# snc98_Display_15x7-Seg_3-digit_LTD056.net
KiCad netlist of a schematic drawn in EAGLE
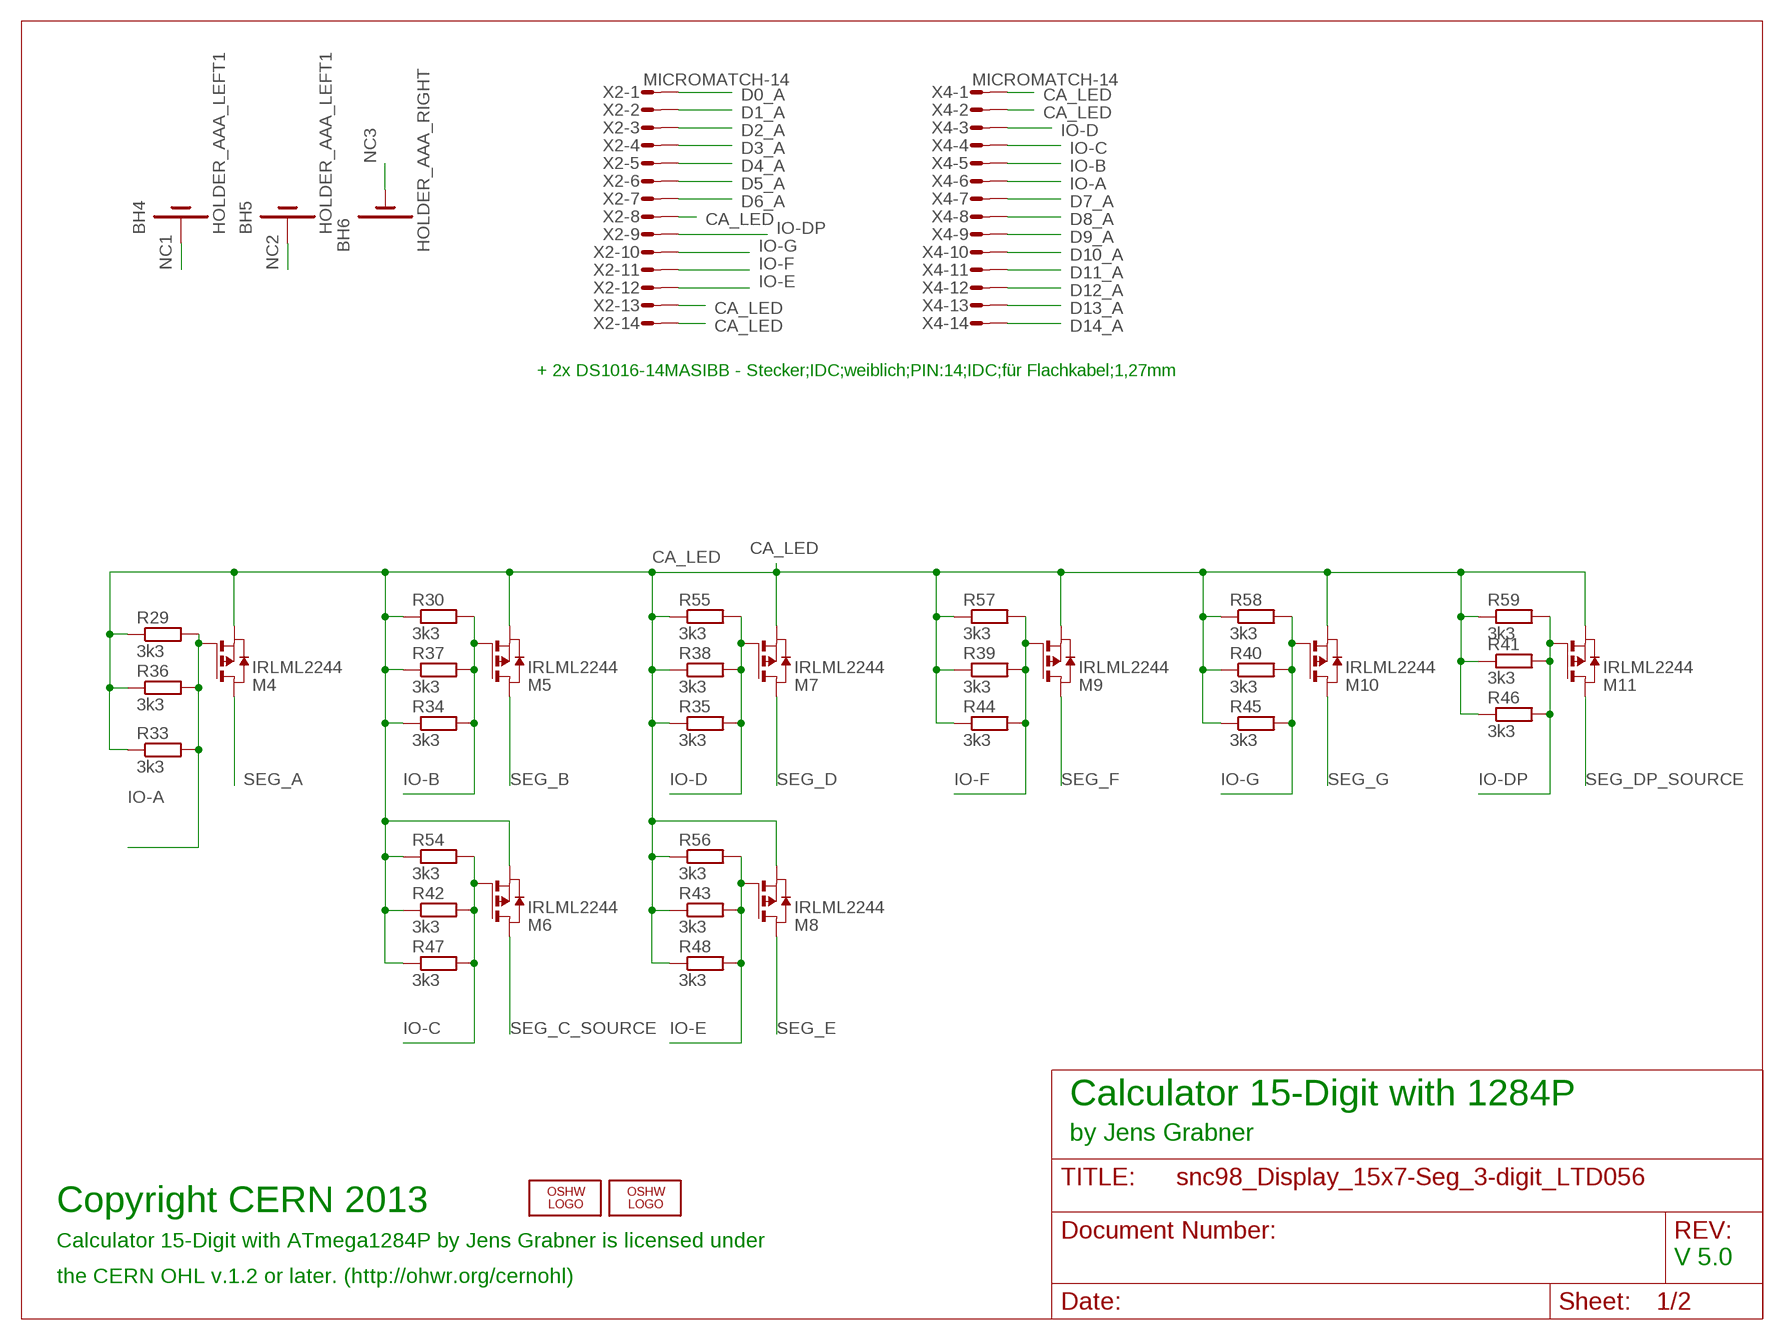
[diagram p0: schematic, sheet 1]
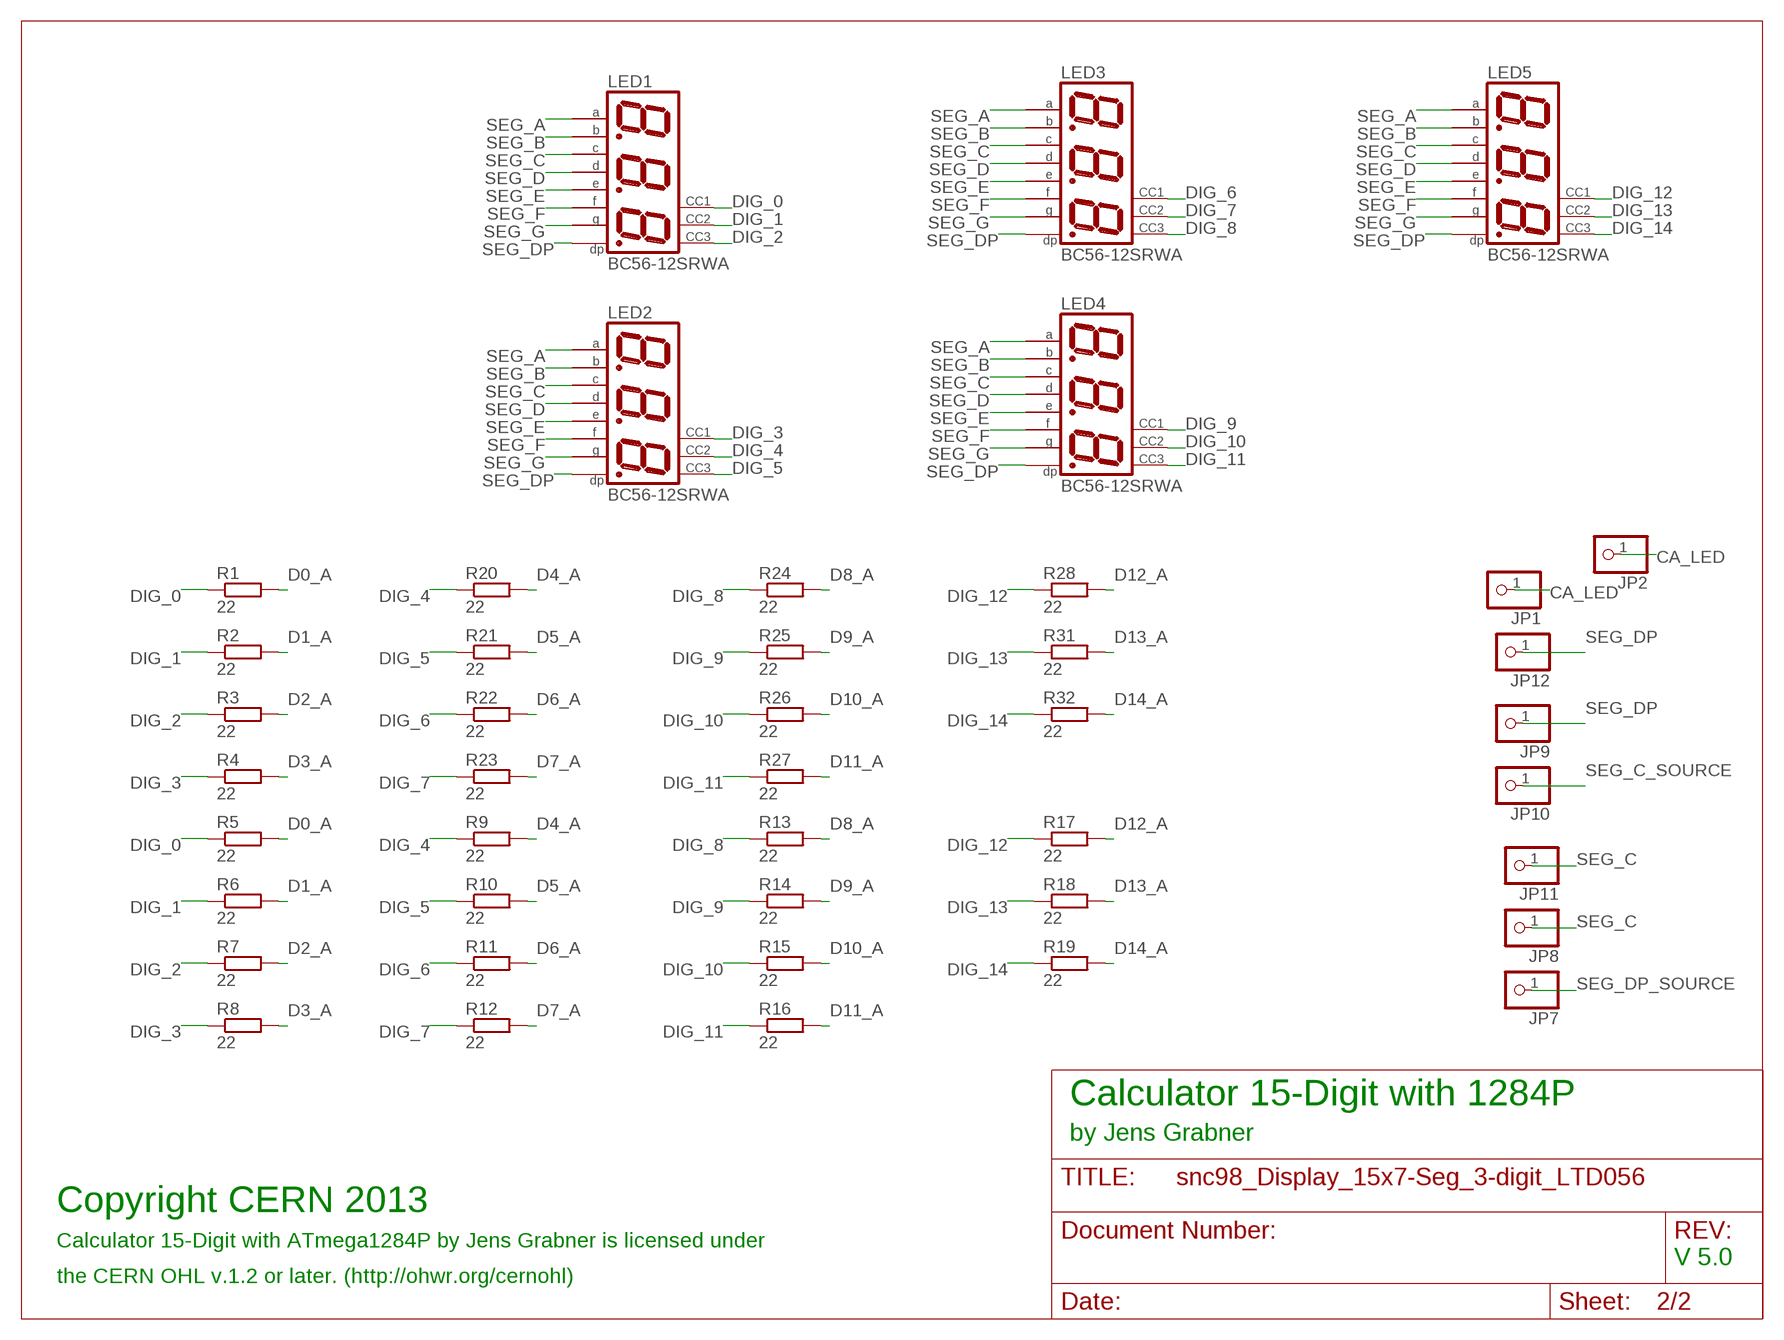
[diagram p1: schematic, sheet 2]

(export (version "E")
  (design (tool "Eeschema 10.0.6"))
  (components
    (comp (ref "BH4")
      (value "HOLDER_AAA_LEFT1")
      (footprint "eagle-import:BATTERY-AAA-LEFT")
      (libsource (lib "eagle-import") (part "HOLDER_AAA_LEFT1"))
    )
    (comp (ref "BH5")
      (value "HOLDER_AAA_LEFT1")
      (footprint "eagle-import:BATTERY-AAA-LEFT")
      (libsource (lib "eagle-import") (part "HOLDER_AAA_LEFT1"))
    )
    (comp (ref "BH6")
      (value "HOLDER_AAA_RIGHT")
      (footprint "eagle-import:BATTERY-AAA-RIGHT")
      (libsource (lib "eagle-import") (part "HOLDER_AAA_RIGHT"))
    )
    (comp (ref "LOGO1")
      (value "OSHW_LOGO_8MILX0150-NT")
      (footprint "eagle-import:OSHW_8X150_NOTEXT")
      (libsource (lib "eagle-import") (part "OSHW_LOGO_8MILX0150-NT"))
    )
    (comp (ref "LOGO3")
      (value "OSHW_LOGO_6MILX0100-NT")
      (footprint "eagle-import:OSHW_6X100_NOTEXT")
      (libsource (lib "eagle-import") (part "OSHW_LOGO_6MILX0100-NT"))
    )
    (comp (ref "M4")
      (value "IRLML2244")
      (footprint "eagle-import:SOT-23")
      (fields (field (name "MF") "INFINEON") (field (name "MPN") "IRLML2244TRPBF"))
      (libsource (lib "eagle-import") (part "IRLML6402"))
    )
    (comp (ref "M5")
      (value "IRLML2244")
      (footprint "eagle-import:SOT-23")
      (fields (field (name "MF") "INFINEON") (field (name "MPN") "IRLML2244TRPBF"))
      (libsource (lib "eagle-import") (part "IRLML6402"))
    )
    (comp (ref "M6")
      (value "IRLML2244")
      (footprint "eagle-import:SOT-23")
      (fields (field (name "MF") "INFINEON") (field (name "MPN") "IRLML2244TRPBF"))
      (libsource (lib "eagle-import") (part "IRLML6402"))
    )
    (comp (ref "M7")
      (value "IRLML2244")
      (footprint "eagle-import:SOT-23")
      (fields (field (name "MF") "INFINEON") (field (name "MPN") "IRLML2244TRPBF"))
      (libsource (lib "eagle-import") (part "IRLML6402"))
    )
    (comp (ref "M8")
      (value "IRLML2244")
      (footprint "eagle-import:SOT-23")
      (fields (field (name "MF") "INFINEON") (field (name "MPN") "IRLML2244TRPBF"))
      (libsource (lib "eagle-import") (part "IRLML6402"))
    )
    (comp (ref "M9")
      (value "IRLML2244")
      (footprint "eagle-import:SOT-23")
      (fields (field (name "MF") "INFINEON") (field (name "MPN") "IRLML2244TRPBF"))
      (libsource (lib "eagle-import") (part "IRLML6402"))
    )
    (comp (ref "M10")
      (value "IRLML2244")
      (footprint "eagle-import:SOT-23")
      (fields (field (name "MF") "INFINEON") (field (name "MPN") "IRLML2244TRPBF"))
      (libsource (lib "eagle-import") (part "IRLML6402"))
    )
    (comp (ref "M11")
      (value "IRLML2244")
      (footprint "eagle-import:SOT-23")
      (fields (field (name "MF") "INFINEON") (field (name "MPN") "IRLML2244TRPBF"))
      (libsource (lib "eagle-import") (part "IRLML6402"))
    )
    (comp (ref "R29")
      (value "3k3")
      (footprint "eagle-import:0204_5")
      (libsource (lib "eagle-import") (part "R-EU_0204/5"))
    )
    (comp (ref "R30")
      (value "3k3")
      (footprint "eagle-import:0204_5")
      (libsource (lib "eagle-import") (part "R-EU_0204/5"))
    )
    (comp (ref "R33")
      (value "3k3")
      (footprint "eagle-import:M0805")
      (libsource (lib "eagle-import") (part "R-EU_M0805"))
    )
    (comp (ref "R34")
      (value "3k3")
      (footprint "eagle-import:M0805")
      (libsource (lib "eagle-import") (part "R-EU_M0805"))
    )
    (comp (ref "R35")
      (value "3k3")
      (footprint "eagle-import:M0805")
      (libsource (lib "eagle-import") (part "R-EU_M0805"))
    )
    (comp (ref "R36")
      (value "3k3")
      (footprint "eagle-import:R1206")
      (libsource (lib "eagle-import") (part "R-EU_R1206"))
    )
    (comp (ref "R37")
      (value "3k3")
      (footprint "eagle-import:R1206")
      (libsource (lib "eagle-import") (part "R-EU_R1206"))
    )
    (comp (ref "R38")
      (value "3k3")
      (footprint "eagle-import:R1206")
      (libsource (lib "eagle-import") (part "R-EU_R1206"))
    )
    (comp (ref "R39")
      (value "3k3")
      (footprint "eagle-import:R1206")
      (libsource (lib "eagle-import") (part "R-EU_R1206"))
    )
    (comp (ref "R40")
      (value "3k3")
      (footprint "eagle-import:R1206")
      (libsource (lib "eagle-import") (part "R-EU_R1206"))
    )
    (comp (ref "R41")
      (value "3k3")
      (footprint "eagle-import:R1206")
      (libsource (lib "eagle-import") (part "R-EU_R1206"))
    )
    (comp (ref "R42")
      (value "3k3")
      (footprint "eagle-import:R1206")
      (libsource (lib "eagle-import") (part "R-EU_R1206"))
    )
    (comp (ref "R43")
      (value "3k3")
      (footprint "eagle-import:R1206")
      (libsource (lib "eagle-import") (part "R-EU_R1206"))
    )
    (comp (ref "R44")
      (value "3k3")
      (footprint "eagle-import:M0805")
      (libsource (lib "eagle-import") (part "R-EU_M0805"))
    )
    (comp (ref "R45")
      (value "3k3")
      (footprint "eagle-import:M0805")
      (libsource (lib "eagle-import") (part "R-EU_M0805"))
    )
    (comp (ref "R46")
      (value "3k3")
      (footprint "eagle-import:M0805")
      (libsource (lib "eagle-import") (part "R-EU_M0805"))
    )
    (comp (ref "R47")
      (value "3k3")
      (footprint "eagle-import:M0805")
      (libsource (lib "eagle-import") (part "R-EU_M0805"))
    )
    (comp (ref "R48")
      (value "3k3")
      (footprint "eagle-import:M0805")
      (libsource (lib "eagle-import") (part "R-EU_M0805"))
    )
    (comp (ref "R54")
      (value "3k3")
      (footprint "eagle-import:0204_5")
      (libsource (lib "eagle-import") (part "R-EU_0204/5"))
    )
    (comp (ref "R55")
      (value "3k3")
      (footprint "eagle-import:0204_5")
      (libsource (lib "eagle-import") (part "R-EU_0204/5"))
    )
    (comp (ref "R56")
      (value "3k3")
      (footprint "eagle-import:0204_5")
      (libsource (lib "eagle-import") (part "R-EU_0204/5"))
    )
    (comp (ref "R57")
      (value "3k3")
      (footprint "eagle-import:0204_5")
      (libsource (lib "eagle-import") (part "R-EU_0204/5"))
    )
    (comp (ref "R58")
      (value "3k3")
      (footprint "eagle-import:0204_5")
      (libsource (lib "eagle-import") (part "R-EU_0204/5"))
    )
    (comp (ref "R59")
      (value "3k3")
      (footprint "eagle-import:0204_5")
      (libsource (lib "eagle-import") (part "R-EU_0204/5"))
    )
    (comp (ref "X2")
      (value "MICROMATCH-14")
      (footprint "eagle-import:MICROMATCH-14")
      (fields
        (field (name "MF") "FARNELL")
        (field (name "MPN") "8-215464-4")
        (field (name "MF_1") "AMP - TE CONNECTIVITY")
      )
      (libsource (lib "eagle-import") (part "MICROMATCH-14"))
    )
    (comp (ref "X4")
      (value "MICROMATCH-14")
      (footprint "eagle-import:MICROMATCH-14")
      (fields
        (field (name "MF") "FARNELL")
        (field (name "MPN") "8-215464-4")
        (field (name "MF_1") "AMP - TE CONNECTIVITY")
      )
      (libsource (lib "eagle-import") (part "MICROMATCH-14"))
    )
    (comp (ref "JP1")
      (value "PINHD-1X1")
      (footprint "eagle-import:1X01")
      (libsource (lib "eagle-import") (part "PINHD-1X1"))
    )
    (comp (ref "JP2")
      (value "PINHD-1X1")
      (footprint "eagle-import:1X01")
      (libsource (lib "eagle-import") (part "PINHD-1X1"))
    )
    (comp (ref "JP7")
      (value "PINHD-1X1")
      (footprint "eagle-import:1X01")
      (libsource (lib "eagle-import") (part "PINHD-1X1"))
    )
    (comp (ref "JP8")
      (value "PINHD-1X1")
      (footprint "eagle-import:1X01")
      (libsource (lib "eagle-import") (part "PINHD-1X1"))
    )
    (comp (ref "JP9")
      (value "PINHD-1X1")
      (footprint "eagle-import:1X01")
      (libsource (lib "eagle-import") (part "PINHD-1X1"))
    )
    (comp (ref "JP10")
      (value "PINHD-1X1")
      (footprint "eagle-import:1X01")
      (libsource (lib "eagle-import") (part "PINHD-1X1"))
    )
    (comp (ref "JP11")
      (value "PINHD-1X1")
      (footprint "eagle-import:1X01")
      (libsource (lib "eagle-import") (part "PINHD-1X1"))
    )
    (comp (ref "JP12")
      (value "PINHD-1X1")
      (footprint "eagle-import:1X01")
      (libsource (lib "eagle-import") (part "PINHD-1X1"))
    )
    (comp (ref "LED1")
      (value "BC56-12SRWA")
      (footprint "eagle-import:BX56-12")
      (libsource (lib "eagle-import") (part "B?56-12WACSR"))
    )
    (comp (ref "LED2")
      (value "BC56-12SRWA")
      (footprint "eagle-import:BX56-12")
      (libsource (lib "eagle-import") (part "B?56-12WACSR"))
    )
    (comp (ref "LED3")
      (value "BC56-12SRWA")
      (footprint "eagle-import:BX56-12")
      (libsource (lib "eagle-import") (part "B?56-12WACSR"))
    )
    (comp (ref "LED4")
      (value "BC56-12SRWA")
      (footprint "eagle-import:BX56-12")
      (libsource (lib "eagle-import") (part "B?56-12WACSR"))
    )
    (comp (ref "LED5")
      (value "BC56-12SRWA")
      (footprint "eagle-import:BX56-12")
      (libsource (lib "eagle-import") (part "B?56-12WACSR"))
    )
    (comp (ref "R1")
      (value "22")
      (footprint "eagle-import:R0805")
      (libsource (lib "eagle-import") (part "R-EU_R0805"))
    )
    (comp (ref "R2")
      (value "22")
      (footprint "eagle-import:R0805")
      (libsource (lib "eagle-import") (part "R-EU_R0805"))
    )
    (comp (ref "R3")
      (value "22")
      (footprint "eagle-import:R0805")
      (libsource (lib "eagle-import") (part "R-EU_R0805"))
    )
    (comp (ref "R4")
      (value "22")
      (footprint "eagle-import:R0805")
      (libsource (lib "eagle-import") (part "R-EU_R0805"))
    )
    (comp (ref "R5")
      (value "22")
      (footprint "eagle-import:R1210")
      (libsource (lib "eagle-import") (part "R-EU_R1210"))
    )
    (comp (ref "R6")
      (value "22")
      (footprint "eagle-import:R1210")
      (libsource (lib "eagle-import") (part "R-EU_R1210"))
    )
    (comp (ref "R7")
      (value "22")
      (footprint "eagle-import:R1210")
      (libsource (lib "eagle-import") (part "R-EU_R1210"))
    )
    (comp (ref "R8")
      (value "22")
      (footprint "eagle-import:R1210")
      (libsource (lib "eagle-import") (part "R-EU_R1210"))
    )
    (comp (ref "R9")
      (value "22")
      (footprint "eagle-import:R1210")
      (libsource (lib "eagle-import") (part "R-EU_R1210"))
    )
    (comp (ref "R10")
      (value "22")
      (footprint "eagle-import:R1210")
      (libsource (lib "eagle-import") (part "R-EU_R1210"))
    )
    (comp (ref "R11")
      (value "22")
      (footprint "eagle-import:R1210")
      (libsource (lib "eagle-import") (part "R-EU_R1210"))
    )
    (comp (ref "R12")
      (value "22")
      (footprint "eagle-import:R1210")
      (libsource (lib "eagle-import") (part "R-EU_R1210"))
    )
    (comp (ref "R13")
      (value "22")
      (footprint "eagle-import:R1210")
      (libsource (lib "eagle-import") (part "R-EU_R1210"))
    )
    (comp (ref "R14")
      (value "22")
      (footprint "eagle-import:R1210")
      (libsource (lib "eagle-import") (part "R-EU_R1210"))
    )
    (comp (ref "R15")
      (value "22")
      (footprint "eagle-import:R1210")
      (libsource (lib "eagle-import") (part "R-EU_R1210"))
    )
    (comp (ref "R16")
      (value "22")
      (footprint "eagle-import:R1210")
      (libsource (lib "eagle-import") (part "R-EU_R1210"))
    )
    (comp (ref "R17")
      (value "22")
      (footprint "eagle-import:R1210")
      (libsource (lib "eagle-import") (part "R-EU_R1210"))
    )
    (comp (ref "R18")
      (value "22")
      (footprint "eagle-import:R1210")
      (libsource (lib "eagle-import") (part "R-EU_R1210"))
    )
    (comp (ref "R19")
      (value "22")
      (footprint "eagle-import:R1210")
      (libsource (lib "eagle-import") (part "R-EU_R1210"))
    )
    (comp (ref "R20")
      (value "22")
      (footprint "eagle-import:R0805")
      (libsource (lib "eagle-import") (part "R-EU_R0805"))
    )
    (comp (ref "R21")
      (value "22")
      (footprint "eagle-import:R0805")
      (libsource (lib "eagle-import") (part "R-EU_R0805"))
    )
    (comp (ref "R22")
      (value "22")
      (footprint "eagle-import:R0805")
      (libsource (lib "eagle-import") (part "R-EU_R0805"))
    )
    (comp (ref "R23")
      (value "22")
      (footprint "eagle-import:R0805")
      (libsource (lib "eagle-import") (part "R-EU_R0805"))
    )
    (comp (ref "R24")
      (value "22")
      (footprint "eagle-import:R0805")
      (libsource (lib "eagle-import") (part "R-EU_R0805"))
    )
    (comp (ref "R25")
      (value "22")
      (footprint "eagle-import:R0805")
      (libsource (lib "eagle-import") (part "R-EU_R0805"))
    )
    (comp (ref "R26")
      (value "22")
      (footprint "eagle-import:R0805")
      (libsource (lib "eagle-import") (part "R-EU_R0805"))
    )
    (comp (ref "R27")
      (value "22")
      (footprint "eagle-import:R0805")
      (libsource (lib "eagle-import") (part "R-EU_R0805"))
    )
    (comp (ref "R28")
      (value "22")
      (footprint "eagle-import:R0805")
      (libsource (lib "eagle-import") (part "R-EU_R0805"))
    )
    (comp (ref "R31")
      (value "22")
      (footprint "eagle-import:R0805")
      (libsource (lib "eagle-import") (part "R-EU_R0805"))
    )
    (comp (ref "R32")
      (value "22")
      (footprint "eagle-import:R0805")
      (libsource (lib "eagle-import") (part "R-EU_R0805"))
    )
  )
  (nets
    (net (code "1") (name "CA_LED") (class "Default")
      (node (ref "JP1") (pin "1") (pinfunction "1_1") (pintype "passive"))
      (node (ref "JP2") (pin "1") (pinfunction "1_1") (pintype "passive"))
      (node (ref "M10") (pin "2") (pinfunction "S_2") (pintype "passive"))
      (node (ref "M11") (pin "2") (pinfunction "S_2") (pintype "passive"))
      (node (ref "M4") (pin "2") (pinfunction "S_2") (pintype "passive"))
      (node (ref "M5") (pin "2") (pinfunction "S_2") (pintype "passive"))
      (node (ref "M6") (pin "2") (pinfunction "S_2") (pintype "passive"))
      (node (ref "M7") (pin "2") (pinfunction "S_2") (pintype "passive"))
      (node (ref "M8") (pin "2") (pinfunction "S_2") (pintype "passive"))
      (node (ref "M9") (pin "2") (pinfunction "S_2") (pintype "passive"))
      (node (ref "R29") (pin "1") (pinfunction "1_1") (pintype "passive"))
      (node (ref "R30") (pin "1") (pinfunction "1_1") (pintype "passive"))
      (node (ref "R33") (pin "1") (pinfunction "1_1") (pintype "passive"))
      (node (ref "R34") (pin "1") (pinfunction "1_1") (pintype "passive"))
      (node (ref "R35") (pin "1") (pinfunction "1_1") (pintype "passive"))
      (node (ref "R36") (pin "1") (pinfunction "1_1") (pintype "passive"))
      (node (ref "R37") (pin "1") (pinfunction "1_1") (pintype "passive"))
      (node (ref "R38") (pin "1") (pinfunction "1_1") (pintype "passive"))
      (node (ref "R39") (pin "1") (pinfunction "1_1") (pintype "passive"))
      (node (ref "R40") (pin "1") (pinfunction "1_1") (pintype "passive"))
      (node (ref "R41") (pin "1") (pinfunction "1_1") (pintype "passive"))
      (node (ref "R42") (pin "1") (pinfunction "1_1") (pintype "passive"))
      (node (ref "R43") (pin "1") (pinfunction "1_1") (pintype "passive"))
      (node (ref "R44") (pin "1") (pinfunction "1_1") (pintype "passive"))
      (node (ref "R45") (pin "1") (pinfunction "1_1") (pintype "passive"))
      (node (ref "R46") (pin "1") (pinfunction "1_1") (pintype "passive"))
      (node (ref "R47") (pin "1") (pinfunction "1_1") (pintype "passive"))
      (node (ref "R48") (pin "1") (pinfunction "1_1") (pintype "passive"))
      (node (ref "R54") (pin "1") (pinfunction "1_1") (pintype "passive"))
      (node (ref "R55") (pin "1") (pinfunction "1_1") (pintype "passive"))
      (node (ref "R56") (pin "1") (pinfunction "1_1") (pintype "passive"))
      (node (ref "R57") (pin "1") (pinfunction "1_1") (pintype "passive"))
      (node (ref "R58") (pin "1") (pinfunction "1_1") (pintype "passive"))
      (node (ref "R59") (pin "1") (pinfunction "1_1") (pintype "passive"))
      (node (ref "X2") (pin "13") (pinfunction "S_13") (pintype "passive"))
      (node (ref "X2") (pin "14") (pinfunction "S_14") (pintype "passive"))
      (node (ref "X2") (pin "8") (pinfunction "S_8") (pintype "passive"))
      (node (ref "X4") (pin "1") (pinfunction "S_1") (pintype "passive"))
      (node (ref "X4") (pin "2") (pinfunction "S_2") (pintype "passive"))
    )
    (net (code "2") (name "D0_A") (class "Default")
      (node (ref "R1") (pin "2") (pinfunction "2_2") (pintype "passive"))
      (node (ref "R5") (pin "2") (pinfunction "2_2") (pintype "passive"))
      (node (ref "X2") (pin "1") (pinfunction "S_1") (pintype "passive"))
    )
    (net (code "3") (name "D1_A") (class "Default")
      (node (ref "R2") (pin "2") (pinfunction "2_2") (pintype "passive"))
      (node (ref "R6") (pin "2") (pinfunction "2_2") (pintype "passive"))
      (node (ref "X2") (pin "2") (pinfunction "S_2") (pintype "passive"))
    )
    (net (code "4") (name "D2_A") (class "Default")
      (node (ref "R3") (pin "2") (pinfunction "2_2") (pintype "passive"))
      (node (ref "R7") (pin "2") (pinfunction "2_2") (pintype "passive"))
      (node (ref "X2") (pin "3") (pinfunction "S_3") (pintype "passive"))
    )
    (net (code "5") (name "D3_A") (class "Default")
      (node (ref "R4") (pin "2") (pinfunction "2_2") (pintype "passive"))
      (node (ref "R8") (pin "2") (pinfunction "2_2") (pintype "passive"))
      (node (ref "X2") (pin "4") (pinfunction "S_4") (pintype "passive"))
    )
    (net (code "6") (name "D4_A") (class "Default")
      (node (ref "R20") (pin "2") (pinfunction "2_2") (pintype "passive"))
      (node (ref "R9") (pin "2") (pinfunction "2_2") (pintype "passive"))
      (node (ref "X2") (pin "5") (pinfunction "S_5") (pintype "passive"))
    )
    (net (code "7") (name "D5_A") (class "Default")
      (node (ref "R10") (pin "2") (pinfunction "2_2") (pintype "passive"))
      (node (ref "R21") (pin "2") (pinfunction "2_2") (pintype "passive"))
      (node (ref "X2") (pin "6") (pinfunction "S_6") (pintype "passive"))
    )
    (net (code "8") (name "D6_A") (class "Default")
      (node (ref "R11") (pin "2") (pinfunction "2_2") (pintype "passive"))
      (node (ref "R22") (pin "2") (pinfunction "2_2") (pintype "passive"))
      (node (ref "X2") (pin "7") (pinfunction "S_7") (pintype "passive"))
    )
    (net (code "9") (name "D7_A") (class "Default")
      (node (ref "R12") (pin "2") (pinfunction "2_2") (pintype "passive"))
      (node (ref "R23") (pin "2") (pinfunction "2_2") (pintype "passive"))
      (node (ref "X4") (pin "7") (pinfunction "S_7") (pintype "passive"))
    )
    (net (code "10") (name "D8_A") (class "Default")
      (node (ref "R13") (pin "2") (pinfunction "2_2") (pintype "passive"))
      (node (ref "R24") (pin "2") (pinfunction "2_2") (pintype "passive"))
      (node (ref "X4") (pin "8") (pinfunction "S_8") (pintype "passive"))
    )
    (net (code "11") (name "D9_A") (class "Default")
      (node (ref "R14") (pin "2") (pinfunction "2_2") (pintype "passive"))
      (node (ref "R25") (pin "2") (pinfunction "2_2") (pintype "passive"))
      (node (ref "X4") (pin "9") (pinfunction "S_9") (pintype "passive"))
    )
    (net (code "12") (name "D10_A") (class "Default")
      (node (ref "R15") (pin "2") (pinfunction "2_2") (pintype "passive"))
      (node (ref "R26") (pin "2") (pinfunction "2_2") (pintype "passive"))
      (node (ref "X4") (pin "10") (pinfunction "S_10") (pintype "passive"))
    )
    (net (code "13") (name "D11_A") (class "Default")
      (node (ref "R16") (pin "2") (pinfunction "2_2") (pintype "passive"))
      (node (ref "R27") (pin "2") (pinfunction "2_2") (pintype "passive"))
      (node (ref "X4") (pin "11") (pinfunction "S_11") (pintype "passive"))
    )
    (net (code "14") (name "D12_A") (class "Default")
      (node (ref "R17") (pin "2") (pinfunction "2_2") (pintype "passive"))
      (node (ref "R28") (pin "2") (pinfunction "2_2") (pintype "passive"))
      (node (ref "X4") (pin "12") (pinfunction "S_12") (pintype "passive"))
    )
    (net (code "15") (name "D13_A") (class "Default")
      (node (ref "R18") (pin "2") (pinfunction "2_2") (pintype "passive"))
      (node (ref "R31") (pin "2") (pinfunction "2_2") (pintype "passive"))
      (node (ref "X4") (pin "13") (pinfunction "S_13") (pintype "passive"))
    )
    (net (code "16") (name "D14_A") (class "Default")
      (node (ref "R19") (pin "2") (pinfunction "2_2") (pintype "passive"))
      (node (ref "R32") (pin "2") (pinfunction "2_2") (pintype "passive"))
      (node (ref "X4") (pin "14") (pinfunction "S_14") (pintype "passive"))
    )
    (net (code "17") (name "DIG_0") (class "Default")
      (node (ref "LED1") (pin "12") (pinfunction "CA_12") (pintype "passive"))
      (node (ref "R1") (pin "1") (pinfunction "1_1") (pintype "passive"))
      (node (ref "R5") (pin "1") (pinfunction "1_1") (pintype "passive"))
    )
    (net (code "18") (name "DIG_1") (class "Default")
      (node (ref "LED1") (pin "9") (pinfunction "CA_9") (pintype "passive"))
      (node (ref "R2") (pin "1") (pinfunction "1_1") (pintype "passive"))
      (node (ref "R6") (pin "1") (pinfunction "1_1") (pintype "passive"))
    )
    (net (code "19") (name "DIG_2") (class "Default")
      (node (ref "LED1") (pin "8") (pinfunction "CA_8") (pintype "passive"))
      (node (ref "R3") (pin "1") (pinfunction "1_1") (pintype "passive"))
      (node (ref "R7") (pin "1") (pinfunction "1_1") (pintype "passive"))
    )
    (net (code "20") (name "DIG_3") (class "Default")
      (node (ref "LED2") (pin "12") (pinfunction "CA_12") (pintype "passive"))
      (node (ref "R4") (pin "1") (pinfunction "1_1") (pintype "passive"))
      (node (ref "R8") (pin "1") (pinfunction "1_1") (pintype "passive"))
    )
    (net (code "21") (name "DIG_4") (class "Default")
      (node (ref "LED2") (pin "9") (pinfunction "CA_9") (pintype "passive"))
      (node (ref "R20") (pin "1") (pinfunction "1_1") (pintype "passive"))
      (node (ref "R9") (pin "1") (pinfunction "1_1") (pintype "passive"))
    )
    (net (code "22") (name "DIG_5") (class "Default")
      (node (ref "LED2") (pin "8") (pinfunction "CA_8") (pintype "passive"))
      (node (ref "R10") (pin "1") (pinfunction "1_1") (pintype "passive"))
      (node (ref "R21") (pin "1") (pinfunction "1_1") (pintype "passive"))
    )
    (net (code "23") (name "DIG_6") (class "Default")
      (node (ref "LED3") (pin "12") (pinfunction "CA_12") (pintype "passive"))
      (node (ref "R11") (pin "1") (pinfunction "1_1") (pintype "passive"))
      (node (ref "R22") (pin "1") (pinfunction "1_1") (pintype "passive"))
    )
    (net (code "24") (name "DIG_7") (class "Default")
      (node (ref "LED3") (pin "9") (pinfunction "CA_9") (pintype "passive"))
      (node (ref "R12") (pin "1") (pinfunction "1_1") (pintype "passive"))
      (node (ref "R23") (pin "1") (pinfunction "1_1") (pintype "passive"))
    )
    (net (code "25") (name "DIG_8") (class "Default")
      (node (ref "LED3") (pin "8") (pinfunction "CA_8") (pintype "passive"))
      (node (ref "R13") (pin "1") (pinfunction "1_1") (pintype "passive"))
      (node (ref "R24") (pin "1") (pinfunction "1_1") (pintype "passive"))
    )
    (net (code "26") (name "DIG_9") (class "Default")
      (node (ref "LED4") (pin "12") (pinfunction "CA_12") (pintype "passive"))
      (node (ref "R14") (pin "1") (pinfunction "1_1") (pintype "passive"))
      (node (ref "R25") (pin "1") (pinfunction "1_1") (pintype "passive"))
    )
    (net (code "27") (name "DIG_10") (class "Default")
      (node (ref "LED4") (pin "9") (pinfunction "CA_9") (pintype "passive"))
      (node (ref "R15") (pin "1") (pinfunction "1_1") (pintype "passive"))
      (node (ref "R26") (pin "1") (pinfunction "1_1") (pintype "passive"))
    )
    (net (code "28") (name "DIG_11") (class "Default")
      (node (ref "LED4") (pin "8") (pinfunction "CA_8") (pintype "passive"))
      (node (ref "R16") (pin "1") (pinfunction "1_1") (pintype "passive"))
      (node (ref "R27") (pin "1") (pinfunction "1_1") (pintype "passive"))
    )
    (net (code "29") (name "DIG_12") (class "Default")
      (node (ref "LED5") (pin "12") (pinfunction "CA_12") (pintype "passive"))
      (node (ref "R17") (pin "1") (pinfunction "1_1") (pintype "passive"))
      (node (ref "R28") (pin "1") (pinfunction "1_1") (pintype "passive"))
    )
    (net (code "30") (name "DIG_13") (class "Default")
      (node (ref "LED5") (pin "9") (pinfunction "CA_9") (pintype "passive"))
      (node (ref "R18") (pin "1") (pinfunction "1_1") (pintype "passive"))
      (node (ref "R31") (pin "1") (pinfunction "1_1") (pintype "passive"))
    )
    (net (code "31") (name "DIG_14") (class "Default")
      (node (ref "LED5") (pin "8") (pinfunction "CA_8") (pintype "passive"))
      (node (ref "R19") (pin "1") (pinfunction "1_1") (pintype "passive"))
      (node (ref "R32") (pin "1") (pinfunction "1_1") (pintype "passive"))
    )
    (net (code "32") (name "IO-A") (class "Default")
      (node (ref "M4") (pin "1") (pinfunction "G_1") (pintype "passive"))
      (node (ref "R29") (pin "2") (pinfunction "2_2") (pintype "passive"))
      (node (ref "R33") (pin "2") (pinfunction "2_2") (pintype "passive"))
      (node (ref "R36") (pin "2") (pinfunction "2_2") (pintype "passive"))
      (node (ref "X4") (pin "6") (pinfunction "S_6") (pintype "passive"))
    )
    (net (code "33") (name "IO-B") (class "Default")
      (node (ref "M5") (pin "1") (pinfunction "G_1") (pintype "passive"))
      (node (ref "R30") (pin "2") (pinfunction "2_2") (pintype "passive"))
      (node (ref "R34") (pin "2") (pinfunction "2_2") (pintype "passive"))
      (node (ref "R37") (pin "2") (pinfunction "2_2") (pintype "passive"))
      (node (ref "X4") (pin "5") (pinfunction "S_5") (pintype "passive"))
    )
    (net (code "34") (name "IO-C") (class "Default")
      (node (ref "M6") (pin "1") (pinfunction "G_1") (pintype "passive"))
      (node (ref "R42") (pin "2") (pinfunction "2_2") (pintype "passive"))
      (node (ref "R47") (pin "2") (pinfunction "2_2") (pintype "passive"))
      (node (ref "R54") (pin "2") (pinfunction "2_2") (pintype "passive"))
      (node (ref "X4") (pin "4") (pinfunction "S_4") (pintype "passive"))
    )
    (net (code "35") (name "IO-D") (class "Default")
      (node (ref "M7") (pin "1") (pinfunction "G_1") (pintype "passive"))
      (node (ref "R35") (pin "2") (pinfunction "2_2") (pintype "passive"))
      (node (ref "R38") (pin "2") (pinfunction "2_2") (pintype "passive"))
      (node (ref "R55") (pin "2") (pinfunction "2_2") (pintype "passive"))
      (node (ref "X4") (pin "3") (pinfunction "S_3") (pintype "passive"))
    )
    (net (code "36") (name "IO-DP") (class "Default")
      (node (ref "M11") (pin "1") (pinfunction "G_1") (pintype "passive"))
      (node (ref "R41") (pin "2") (pinfunction "2_2") (pintype "passive"))
      (node (ref "R46") (pin "2") (pinfunction "2_2") (pintype "passive"))
      (node (ref "R59") (pin "2") (pinfunction "2_2") (pintype "passive"))
      (node (ref "X2") (pin "9") (pinfunction "S_9") (pintype "passive"))
    )
    (net (code "37") (name "IO-E") (class "Default")
      (node (ref "M8") (pin "1") (pinfunction "G_1") (pintype "passive"))
      (node (ref "R43") (pin "2") (pinfunction "2_2") (pintype "passive"))
      (node (ref "R48") (pin "2") (pinfunction "2_2") (pintype "passive"))
      (node (ref "R56") (pin "2") (pinfunction "2_2") (pintype "passive"))
      (node (ref "X2") (pin "12") (pinfunction "S_12") (pintype "passive"))
    )
    (net (code "38") (name "IO-F") (class "Default")
      (node (ref "M9") (pin "1") (pinfunction "G_1") (pintype "passive"))
      (node (ref "R39") (pin "2") (pinfunction "2_2") (pintype "passive"))
      (node (ref "R44") (pin "2") (pinfunction "2_2") (pintype "passive"))
      (node (ref "R57") (pin "2") (pinfunction "2_2") (pintype "passive"))
      (node (ref "X2") (pin "11") (pinfunction "S_11") (pintype "passive"))
    )
    (net (code "39") (name "IO-G") (class "Default")
      (node (ref "M10") (pin "1") (pinfunction "G_1") (pintype "passive"))
      (node (ref "R40") (pin "2") (pinfunction "2_2") (pintype "passive"))
      (node (ref "R45") (pin "2") (pinfunction "2_2") (pintype "passive"))
      (node (ref "R58") (pin "2") (pinfunction "2_2") (pintype "passive"))
      (node (ref "X2") (pin "10") (pinfunction "S_10") (pintype "passive"))
    )
    (net (code "40") (name "NC1") (class "Default")
      (node (ref "BH4") (pin "P1") (pinfunction "+_P1") (pintype "power_in"))
      (node (ref "BH4") (pin "P2") (pinfunction "+_P2") (pintype "power_in"))
      (node (ref "BH4") (pin "P3") (pinfunction "+_P3") (pintype "power_in"))
      (node (ref "BH4") (pin "P4") (pinfunction "+_P4") (pintype "power_in"))
    )
    (net (code "41") (name "NC2") (class "Default")
      (node (ref "BH5") (pin "P1") (pinfunction "+_P1") (pintype "power_in"))
      (node (ref "BH5") (pin "P2") (pinfunction "+_P2") (pintype "power_in"))
      (node (ref "BH5") (pin "P3") (pinfunction "+_P3") (pintype "power_in"))
      (node (ref "BH5") (pin "P4") (pinfunction "+_P4") (pintype "power_in"))
    )
    (net (code "42") (name "NC3") (class "Default")
      (node (ref "BH6") (pin "M1") (pinfunction "-_M1") (pintype "power_in"))
      (node (ref "BH6") (pin "M2") (pinfunction "-_M2") (pintype "power_in"))
      (node (ref "BH6") (pin "M3") (pinfunction "-_M3") (pintype "power_in"))
      (node (ref "BH6") (pin "M4") (pinfunction "-_M4") (pintype "power_in"))
    )
    (net (code "43") (name "SEG_A") (class "Default")
      (node (ref "LED1") (pin "11") (pinfunction "A_11") (pintype "passive"))
      (node (ref "LED2") (pin "11") (pinfunction "A_11") (pintype "passive"))
      (node (ref "LED3") (pin "11") (pinfunction "A_11") (pintype "passive"))
      (node (ref "LED4") (pin "11") (pinfunction "A_11") (pintype "passive"))
      (node (ref "LED5") (pin "11") (pinfunction "A_11") (pintype "passive"))
      (node (ref "M4") (pin "3") (pinfunction "D_3") (pintype "passive"))
    )
    (net (code "44") (name "SEG_B") (class "Default")
      (node (ref "LED1") (pin "7") (pinfunction "B_7") (pintype "passive"))
      (node (ref "LED2") (pin "7") (pinfunction "B_7") (pintype "passive"))
      (node (ref "LED3") (pin "7") (pinfunction "B_7") (pintype "passive"))
      (node (ref "LED4") (pin "7") (pinfunction "B_7") (pintype "passive"))
      (node (ref "LED5") (pin "7") (pinfunction "B_7") (pintype "passive"))
      (node (ref "M5") (pin "3") (pinfunction "D_3") (pintype "passive"))
    )
    (net (code "45") (name "SEG_C") (class "Default")
      (node (ref "JP11") (pin "1") (pinfunction "1_1") (pintype "passive"))
      (node (ref "JP8") (pin "1") (pinfunction "1_1") (pintype "passive"))
      (node (ref "LED1") (pin "4") (pinfunction "C_4") (pintype "passive"))
      (node (ref "LED2") (pin "4") (pinfunction "C_4") (pintype "passive"))
      (node (ref "LED3") (pin "4") (pinfunction "C_4") (pintype "passive"))
      (node (ref "LED4") (pin "4") (pinfunction "C_4") (pintype "passive"))
      (node (ref "LED5") (pin "4") (pinfunction "C_4") (pintype "passive"))
    )
    (net (code "46") (name "SEG_C_SOURCE") (class "Default")
      (node (ref "JP10") (pin "1") (pinfunction "1_1") (pintype "passive"))
      (node (ref "M6") (pin "3") (pinfunction "D_3") (pintype "passive"))
    )
    (net (code "47") (name "SEG_D") (class "Default")
      (node (ref "LED1") (pin "2") (pinfunction "D_2") (pintype "passive"))
      (node (ref "LED2") (pin "2") (pinfunction "D_2") (pintype "passive"))
      (node (ref "LED3") (pin "2") (pinfunction "D_2") (pintype "passive"))
      (node (ref "LED4") (pin "2") (pinfunction "D_2") (pintype "passive"))
      (node (ref "LED5") (pin "2") (pinfunction "D_2") (pintype "passive"))
      (node (ref "M7") (pin "3") (pinfunction "D_3") (pintype "passive"))
    )
    (net (code "48") (name "SEG_DP") (class "Default")
      (node (ref "JP12") (pin "1") (pinfunction "1_1") (pintype "passive"))
      (node (ref "JP9") (pin "1") (pinfunction "1_1") (pintype "passive"))
      (node (ref "LED1") (pin "3") (pinfunction "DP_3") (pintype "passive"))
      (node (ref "LED2") (pin "3") (pinfunction "DP_3") (pintype "passive"))
      (node (ref "LED3") (pin "3") (pinfunction "DP_3") (pintype "passive"))
      (node (ref "LED4") (pin "3") (pinfunction "DP_3") (pintype "passive"))
      (node (ref "LED5") (pin "3") (pinfunction "DP_3") (pintype "passive"))
    )
    (net (code "49") (name "SEG_DP_SOURCE") (class "Default")
      (node (ref "JP7") (pin "1") (pinfunction "1_1") (pintype "passive"))
      (node (ref "M11") (pin "3") (pinfunction "D_3") (pintype "passive"))
    )
    (net (code "50") (name "SEG_E") (class "Default")
      (node (ref "LED1") (pin "1") (pinfunction "E_1") (pintype "passive"))
      (node (ref "LED2") (pin "1") (pinfunction "E_1") (pintype "passive"))
      (node (ref "LED3") (pin "1") (pinfunction "E_1") (pintype "passive"))
      (node (ref "LED4") (pin "1") (pinfunction "E_1") (pintype "passive"))
      (node (ref "LED5") (pin "1") (pinfunction "E_1") (pintype "passive"))
      (node (ref "M8") (pin "3") (pinfunction "D_3") (pintype "passive"))
    )
    (net (code "51") (name "SEG_F") (class "Default")
      (node (ref "LED1") (pin "10") (pinfunction "F_10") (pintype "passive"))
      (node (ref "LED2") (pin "10") (pinfunction "F_10") (pintype "passive"))
      (node (ref "LED3") (pin "10") (pinfunction "F_10") (pintype "passive"))
      (node (ref "LED4") (pin "10") (pinfunction "F_10") (pintype "passive"))
      (node (ref "LED5") (pin "10") (pinfunction "F_10") (pintype "passive"))
      (node (ref "M9") (pin "3") (pinfunction "D_3") (pintype "passive"))
    )
    (net (code "52") (name "SEG_G") (class "Default")
      (node (ref "LED1") (pin "5") (pinfunction "G_5") (pintype "passive"))
      (node (ref "LED2") (pin "5") (pinfunction "G_5") (pintype "passive"))
      (node (ref "LED3") (pin "5") (pinfunction "G_5") (pintype "passive"))
      (node (ref "LED4") (pin "5") (pinfunction "G_5") (pintype "passive"))
      (node (ref "LED5") (pin "5") (pinfunction "G_5") (pintype "passive"))
      (node (ref "M10") (pin "3") (pinfunction "D_3") (pintype "passive"))
    )
  )
)
